# Misc.net
KiCad netlist of a schematic drawn in Altium Designer
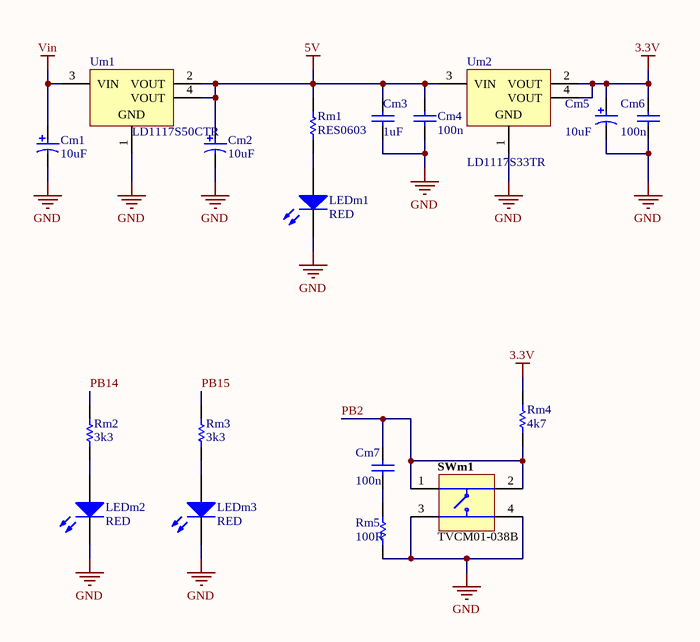
[diagram p0: Misc.SchDoc]

(export (version "E")
  (design (tool "Eeschema 10.0.6"))
  (components
    (comp (ref "Cm1")
      (value "10uF")
      (footprint "CAPMP3217X18-T_V")
      (description "Standard Tantalum, 1 uF, +/- 10%, 35 V, -55 to 125 degC, 2-Pin SMD (1206), RoHS, Tape and Reel")
      (libsource (lib "Altium Content Vault") (part "CAP-P-2"))
    )
    (comp (ref "Cm2")
      (value "10uF")
      (footprint "CAPMP3217X18-T_V")
      (description "Standard Tantalum, 1 uF, +/- 10%, 35 V, -55 to 125 degC, 2-Pin SMD (1206), RoHS, Tape and Reel")
      (libsource (lib "Altium Content Vault") (part "CAP-P-2"))
    )
    (comp (ref "Cm3")
      (value "1uF")
      (footprint "CAPC0603(1608)100_L")
      (description "0603 (1608 Metric) Chip Capacitor")
      (libsource (lib "Altium Content Vault") (part "CAP_5"))
    )
    (comp (ref "Cm4")
      (value "100n")
      (footprint "CAPC0603(1608)100_L")
      (description "0603 (1608 Metric) Chip Capacitor")
      (libsource (lib "Altium Content Vault") (part "CAP_5"))
    )
    (comp (ref "Cm5")
      (value "10uF")
      (footprint "CAPMP3217X18-T_V")
      (description "Standard Tantalum, 1 uF, +/- 10%, 35 V, -55 to 125 degC, 2-Pin SMD (1206), RoHS, Tape and Reel")
      (libsource (lib "Altium Content Vault") (part "CAP-P-2"))
    )
    (comp (ref "Cm6")
      (value "100n")
      (footprint "CAPC0603(1608)100_L")
      (description "0603 (1608 Metric) Chip Capacitor")
      (libsource (lib "Altium Content Vault") (part "CAP_5"))
    )
    (comp (ref "Cm7")
      (value "100n")
      (footprint "CAPC0603(1608)100_L")
      (description "0603 (1608 Metric) Chip Capacitor")
      (libsource (lib "Altium Content Vault") (part "CAP_5"))
    )
    (comp (ref "LEDm1")
      (value "RED")
      (footprint "0805_DIODE")
      (description "Light-emitting diode")
      (libsource (lib "Library_Altium") (part "LED"))
    )
    (comp (ref "LEDm2")
      (value "RED")
      (footprint "0805_DIODE")
      (description "Light-emitting diode")
      (libsource (lib "Library_Altium") (part "LED"))
    )
    (comp (ref "LEDm3")
      (value "RED")
      (footprint "0805_DIODE")
      (description "Light-emitting diode")
      (libsource (lib "Library_Altium") (part "LED"))
    )
    (comp (ref "Rm1")
      (value "RES0603")
      (footprint "RESC0603(1608)_L")
      (description "0603 (1608 Metric) Chip Resistor")
      (libsource (lib "Altium Content Vault") (part "RES_3"))
    )
    (comp (ref "Rm2")
      (value "3k3")
      (footprint "RESC0603(1608)_L")
      (description "0603 (1608 Metric) Chip Resistor")
      (libsource (lib "Altium Content Vault") (part "RES_3"))
    )
    (comp (ref "Rm3")
      (value "3k3")
      (footprint "RESC0603(1608)_L")
      (description "0603 (1608 Metric) Chip Resistor")
      (libsource (lib "Altium Content Vault") (part "RES_3"))
    )
    (comp (ref "Rm4")
      (value "4k7")
      (footprint "RESC0603(1608)_L")
      (description "0603 (1608 Metric) Chip Resistor")
      (libsource (lib "Altium Content Vault") (part "RES_3"))
    )
    (comp (ref "Rm5")
      (value "100R")
      (footprint "RESC0603(1608)_L")
      (description "0603 (1608 Metric) Chip Resistor")
      (libsource (lib "Altium Content Vault") (part "RES_3"))
    )
    (comp (ref "SWm1")
      (value "TVCM01-038B")
      (footprint "JNFU-TVCM01-038B_V")
      (description "Switch, Push Button, 50 mA, 12V DC, SMD")
      (libsource (lib "Altium Content Vault") (part "JNFU-TVCM01-038B-4"))
    )
    (comp (ref "Um1")
      (value "LD1117S50CTR")
      (footprint "SOT-223_N")
      (description "Fixed Low Drop Positive Voltage Regulator, 5V, 4-Pin SOT-223, Tape and Reel")
      (libsource (lib "Altium Content Vault") (part "PM-REG-LD1117-SOT4"))
    )
    (comp (ref "Um2")
      (value "LD1117S33TR")
      (footprint "SOT-223_L")
      (description "Fixed Low Drop Positive Voltage Regulator, 3.3V, 4-Pin SOT-223, Tape and Reel")
      (libsource (lib "Altium Content Vault") (part "PM-REG-LD1117-SOT4"))
    )
  )
  (nets
    (net (code "1") (name "/PB2") (class "Default")
      (node (ref "Cm7") (pin "2") (pinfunction "2_2") (pintype "passive"))
      (node (ref "Rm4") (pin "1") (pinfunction "1_1") (pintype "passive"))
      (node (ref "SWm1") (pin "1") (pinfunction "1_1") (pintype "passive"))
      (node (ref "SWm1") (pin "2") (pinfunction "2_2") (pintype "passive"))
    )
    (net (code "2") (name "/PB14") (class "Default")
      (node (ref "Rm2") (pin "2") (pinfunction "2_2") (pintype "passive"))
    )
    (net (code "3") (name "/PB15") (class "Default")
      (node (ref "Rm3") (pin "2") (pinfunction "2_2") (pintype "passive"))
    )
    (net (code "4") (name "3.3V") (class "Default")
      (node (ref "Cm5") (pin "1") (pinfunction "1_1") (pintype "passive"))
      (node (ref "Cm6") (pin "2") (pinfunction "2_2") (pintype "passive"))
      (node (ref "Rm4") (pin "2") (pinfunction "2_2") (pintype "passive"))
      (node (ref "Um2") (pin "2") (pinfunction "VOUT_2") (pintype "power_in"))
      (node (ref "Um2") (pin "4") (pinfunction "VOUT_4") (pintype "power_in"))
    )
    (net (code "5") (name "5V") (class "Default")
      (node (ref "Cm2") (pin "1") (pinfunction "1_1") (pintype "passive"))
      (node (ref "Cm3") (pin "2") (pinfunction "2_2") (pintype "passive"))
      (node (ref "Cm4") (pin "2") (pinfunction "2_2") (pintype "passive"))
      (node (ref "Rm1") (pin "2") (pinfunction "2_2") (pintype "passive"))
      (node (ref "Um1") (pin "2") (pinfunction "VOUT_2") (pintype "power_in"))
      (node (ref "Um1") (pin "4") (pinfunction "VOUT_4") (pintype "power_in"))
      (node (ref "Um2") (pin "3") (pinfunction "VIN_3") (pintype "power_in"))
    )
    (net (code "6") (name "GND") (class "Default")
      (node (ref "Cm1") (pin "2") (pinfunction "2_2") (pintype "passive"))
      (node (ref "Cm2") (pin "2") (pinfunction "2_2") (pintype "passive"))
      (node (ref "Cm3") (pin "1") (pinfunction "1_1") (pintype "passive"))
      (node (ref "Cm4") (pin "1") (pinfunction "1_1") (pintype "passive"))
      (node (ref "Cm5") (pin "2") (pinfunction "2_2") (pintype "passive"))
      (node (ref "Cm6") (pin "1") (pinfunction "1_1") (pintype "passive"))
      (node (ref "LEDm1") (pin "2") (pinfunction "K_2") (pintype "passive"))
      (node (ref "LEDm2") (pin "2") (pinfunction "K_2") (pintype "passive"))
      (node (ref "LEDm3") (pin "2") (pinfunction "K_2") (pintype "passive"))
      (node (ref "Rm5") (pin "1") (pinfunction "1_1") (pintype "passive"))
      (node (ref "SWm1") (pin "3") (pinfunction "3_3") (pintype "passive"))
      (node (ref "SWm1") (pin "4") (pinfunction "4_4") (pintype "passive"))
      (node (ref "Um1") (pin "1") (pinfunction "GND_1") (pintype "power_in"))
      (node (ref "Um2") (pin "1") (pinfunction "GND_1") (pintype "power_in"))
    )
    (net (code "7") (name "Net-(Cm7-Pad1)") (class "Default")
      (node (ref "Cm7") (pin "1") (pinfunction "1_1") (pintype "passive"))
      (node (ref "Rm5") (pin "2") (pinfunction "2_2") (pintype "passive"))
    )
    (net (code "8") (name "Net-(LEDm1-A)") (class "Default")
      (node (ref "LEDm1") (pin "1") (pinfunction "A_1") (pintype "passive"))
      (node (ref "Rm1") (pin "1") (pinfunction "1_1") (pintype "passive"))
    )
    (net (code "9") (name "Net-(LEDm2-A)") (class "Default")
      (node (ref "LEDm2") (pin "1") (pinfunction "A_1") (pintype "passive"))
      (node (ref "Rm2") (pin "1") (pinfunction "1_1") (pintype "passive"))
    )
    (net (code "10") (name "Net-(LEDm3-A)") (class "Default")
      (node (ref "LEDm3") (pin "1") (pinfunction "A_1") (pintype "passive"))
      (node (ref "Rm3") (pin "1") (pinfunction "1_1") (pintype "passive"))
    )
    (net (code "11") (name "Vin") (class "Default")
      (node (ref "Cm1") (pin "1") (pinfunction "1_1") (pintype "passive"))
      (node (ref "Um1") (pin "3") (pinfunction "VIN_3") (pintype "power_in"))
    )
  )
)
